# Pressure_Sensor.net
KiCad netlist of a schematic drawn in Altium Designer
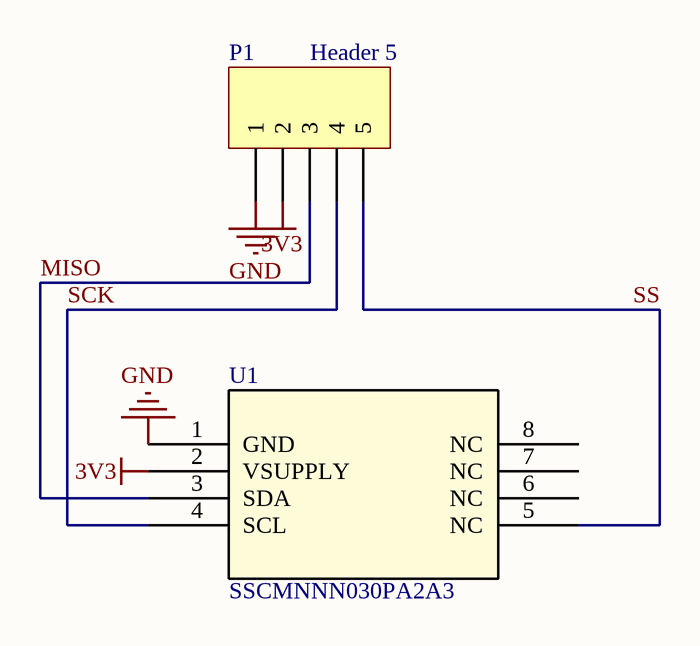
[diagram p0: Pressure Sensor.SchDoc]

(export (version "E")
  (design (tool "Eeschema 10.0.6"))
  (components
    (comp (ref "P1")
      (value "Header 5")
      (footprint "CONN_B5B-XH-A (LF)(SN)_JST")
      (description "Header, 5-Pin")
      (fields (field (name "PUBLISHER") "Altium Limited"))
      (libsource (lib "Miscellaneous Connectors") (part "Header 5"))
    )
    (comp (ref "U1")
      (value "SSCMNNN030PA2A3")
      (footprint "SSCMNN_HNW-L")
      (description "No Description Available")
      (fields (field (name "COPYRIGHT") "Copyright (C) 2018 Accelerated Designs. All rights reserved"))
      (libsource (lib "2020-10-01_16-01-06") (part "SSCMNNN030PA2A3"))
    )
  )
  (nets
    (net (code "1") (name "/MISO") (class "Default")
      (node (ref "P1") (pin "3") (pinfunction "3_3") (pintype "passive"))
      (node (ref "U1") (pin "3") (pinfunction "SDA_3") (pintype "passive"))
    )
    (net (code "2") (name "/SCK") (class "Default")
      (node (ref "P1") (pin "4") (pinfunction "4_4") (pintype "passive"))
      (node (ref "U1") (pin "4") (pinfunction "SCL_4") (pintype "passive"))
    )
    (net (code "3") (name "/SS") (class "Default")
      (node (ref "P1") (pin "5") (pinfunction "5_5") (pintype "passive"))
      (node (ref "U1") (pin "5") (pinfunction "NC_5") (pintype "passive"))
    )
    (net (code "4") (name "3V3") (class "Default")
      (node (ref "P1") (pin "2") (pinfunction "2_2") (pintype "passive"))
      (node (ref "U1") (pin "2") (pinfunction "VSUPPLY_2") (pintype "power_in"))
    )
    (net (code "5") (name "GND") (class "Default")
      (node (ref "P1") (pin "1") (pinfunction "1_1") (pintype "passive"))
      (node (ref "U1") (pin "1") (pinfunction "GND_1") (pintype "passive"))
    )
    (net (code "6") (name "unconnected-(U1-NC-Pad6)") (class "Default")
      (node (ref "U1") (pin "6") (pinfunction "NC_6") (pintype "passive"))
    )
    (net (code "7") (name "unconnected-(U1-NC-Pad7)") (class "Default")
      (node (ref "U1") (pin "7") (pinfunction "NC_7") (pintype "passive"))
    )
    (net (code "8") (name "unconnected-(U1-NC-Pad8)") (class "Default")
      (node (ref "U1") (pin "8") (pinfunction "NC_8") (pintype "passive"))
    )
  )
)
